# dasblinkenhat-controller-mk-4_2.net
KiCad netlist of a schematic drawn in EAGLE
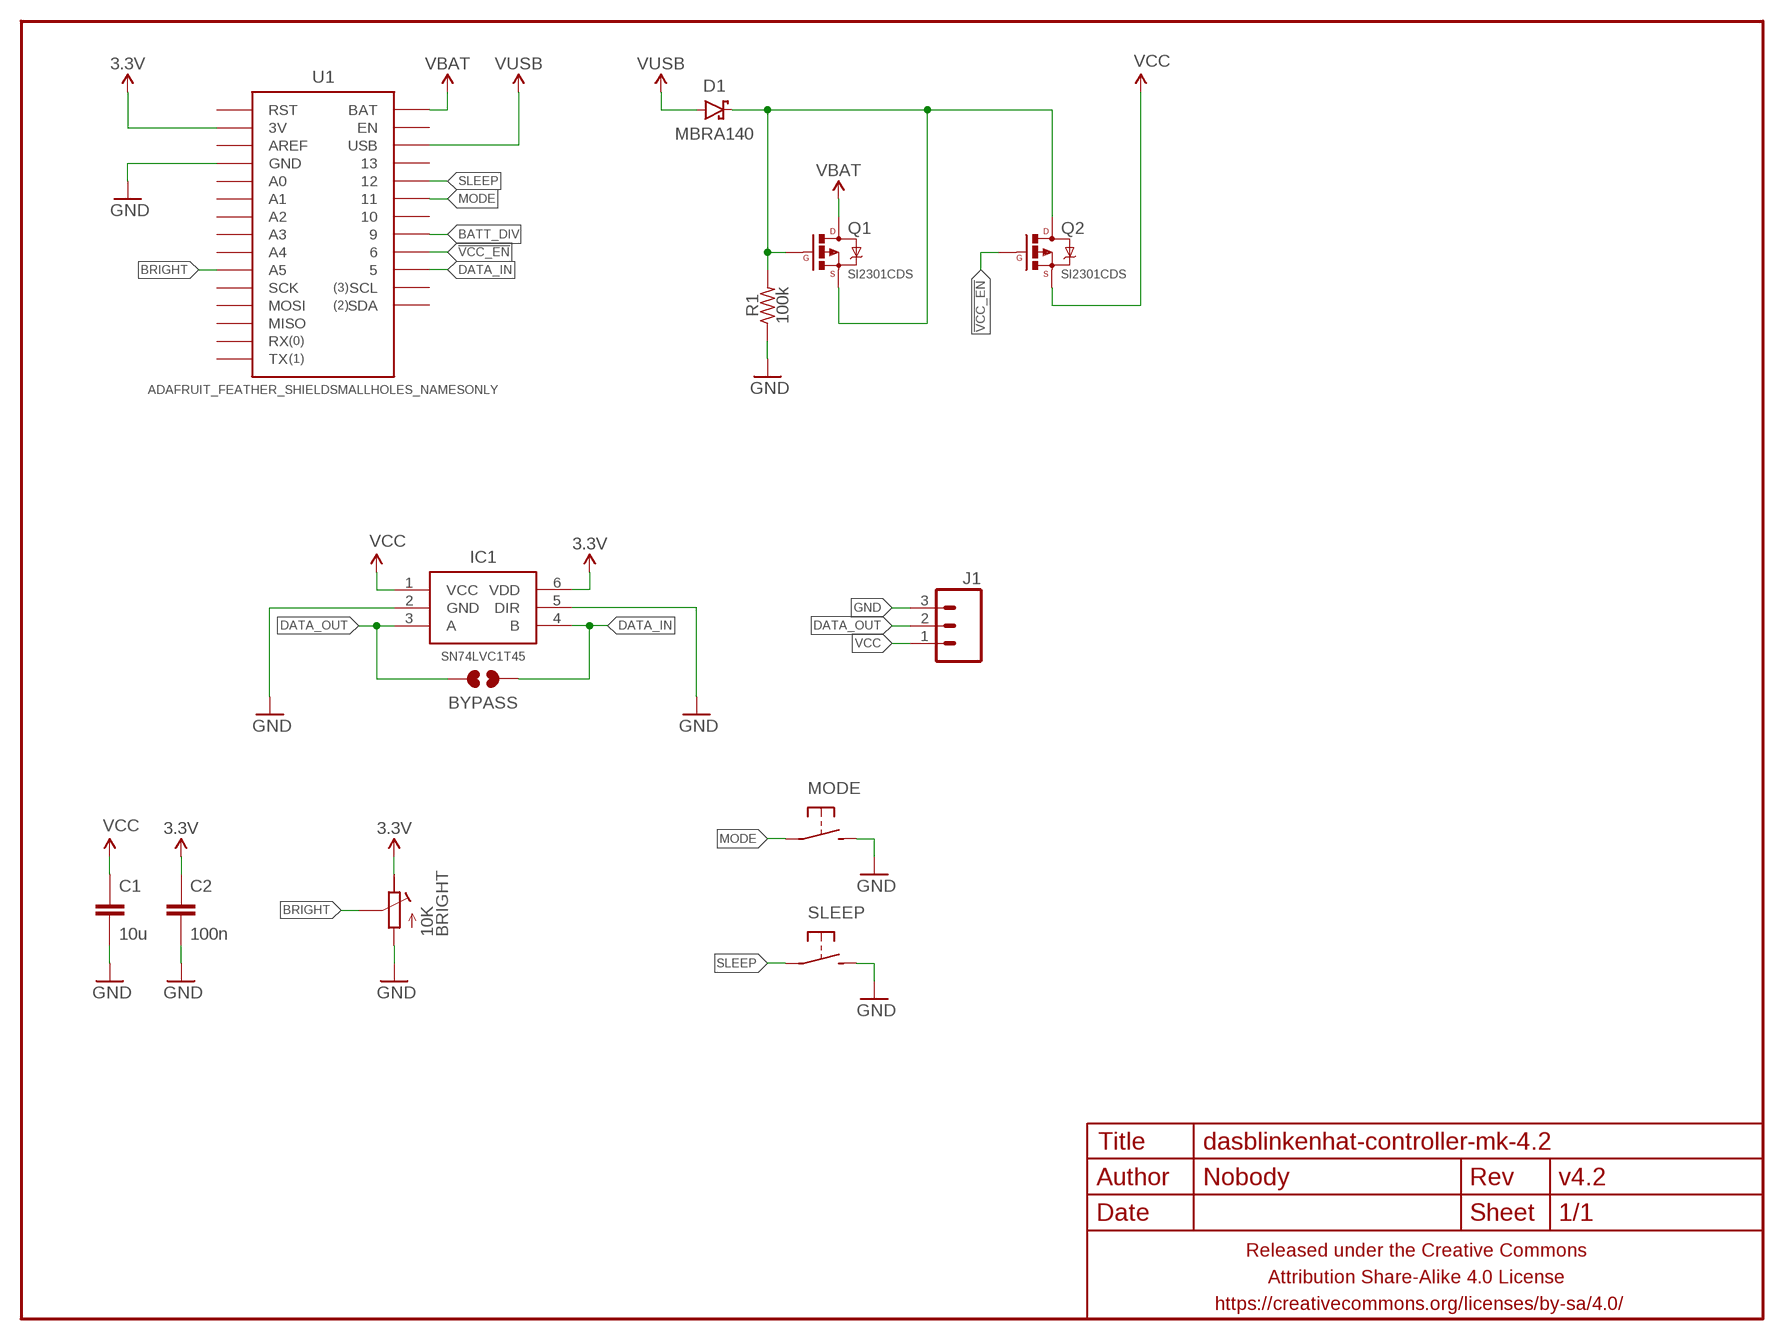
[diagram p0: schematic, sheet 1]

(export (version "E")
  (design (tool "Eeschema 10.0.6"))
  (components
    (comp (ref "BRIGHT")
      (value "10K")
      (footprint "eagle-import:EVM3Y")
      (libsource (lib "eagle-import") (part "POTENTIOMETEREVM3Y"))
    )
    (comp (ref "BYPASS")
      (value "JUMPER-PAD-2-NOYES_SILK")
      (footprint "eagle-import:PAD-JUMPER-2-NO_YES_SILK")
      (libsource (lib "eagle-import") (part "JUMPER-PAD-2-NOYES_SILK"))
    )
    (comp (ref "C1")
      (value "10u")
      (footprint "eagle-import:C0805")
      (libsource (lib "eagle-import") (part "CAPACITOR-CERAMICC0805"))
    )
    (comp (ref "C2")
      (value "100n")
      (footprint "eagle-import:C0603")
      (libsource (lib "eagle-import") (part "CAPACITOR-CERAMICC0603"))
    )
    (comp (ref "D1")
      (value "MBRA140")
      (footprint "eagle-import:SMA-DIODE")
      (libsource (lib "eagle-import") (part "DIODE-SCHOTTKYMBRA140"))
    )
    (comp (ref "FRAME1")
      (value "FRAME-LETTERNO_PACKAGE")
      (footprint "eagle-import:DUMMY")
      (fields (field (name "VERSION") "v4.2") (field (name "DESIGNER") "Nobody"))
      (libsource (lib "eagle-import") (part "FRAME-LETTERNO_PACKAGE"))
    )
    (comp (ref "IC1")
      (value "SN74LVC1T45")
      (footprint "eagle-import:SOT23-6")
      (libsource (lib "eagle-import") (part "SN74LVC1T45SOT23-6"))
    )
    (comp (ref "J1")
      (value "M03JST-XH-RA-PTH")
      (footprint "eagle-import:JST-3-XH-RA-PTH")
      (libsource (lib "eagle-import") (part "M03JST-XH-RA-PTH"))
    )
    (comp (ref "MODE")
      (value "DTS-6MM")
      (footprint "eagle-import:TACTILE-PTH-12MM")
      (libsource (lib "eagle-import") (part "SPST-NO-TACT12MM-PTH"))
    )
    (comp (ref "Q1")
      (value "SI2301CDS")
      (footprint "eagle-import:SOT23")
      (libsource (lib "eagle-import") (part "MOSFET-PCHANNELSOT-23"))
    )
    (comp (ref "Q2")
      (value "SI2301CDS")
      (footprint "eagle-import:SOT23")
      (libsource (lib "eagle-import") (part "MOSFET-PCHANNELSOT-23"))
    )
    (comp (ref "R1")
      (value "100k")
      (footprint "eagle-import:R0603")
      (libsource (lib "eagle-import") (part "RESISTORR0603"))
    )
    (comp (ref "SLEEP")
      (value "DTS-6MM")
      (footprint "eagle-import:TACTILE-PTH-12MM")
      (libsource (lib "eagle-import") (part "SPST-NO-TACT12MM-PTH"))
    )
    (comp (ref "U1")
      (value "ADAFRUIT_FEATHER_SHIELDSMALLHOLES_NAMESONLY")
      (footprint "eagle-import:ADAFRUIT_FEATHER_SMALLHOLES_NAMESONLY")
      (libsource (lib "eagle-import") (part "ADAFRUIT_FEATHER_SHIELDSMALLHOLES_NAMESONLY"))
    )
  )
  (nets
    (net (code "1") (name "/~{VCC_EN}") (class "Default")
      (node (ref "Q2") (pin "1") (pinfunction "G_1") (pintype "passive"))
      (node (ref "U1") (pin "6") (pinfunction "6_6") (pintype "bidirectional"))
    )
    (net (code "2") (name "3.3V") (class "Default")
      (node (ref "BRIGHT") (pin "E") (pinfunction "E_E") (pintype "passive"))
      (node (ref "C2") (pin "1") (pinfunction "1_1") (pintype "passive"))
      (node (ref "IC1") (pin "6") (pinfunction "VDD_6") (pintype "bidirectional"))
      (node (ref "U1") (pin "3V") (pinfunction "3V_3V") (pintype "bidirectional"))
    )
    (net (code "3") (name "BATT_DIV") (class "Default")
      (node (ref "U1") (pin "9") (pinfunction "9_9") (pintype "bidirectional"))
    )
    (net (code "4") (name "BRIGHT") (class "Default")
      (node (ref "BRIGHT") (pin "S") (pinfunction "S_S") (pintype "passive"))
      (node (ref "U1") (pin "A5") (pinfunction "A5_A5") (pintype "bidirectional"))
    )
    (net (code "5") (name "DATA_IN") (class "Default")
      (node (ref "BYPASS") (pin "1") (pinfunction "1_1") (pintype "passive"))
      (node (ref "IC1") (pin "4") (pinfunction "B_4") (pintype "bidirectional"))
      (node (ref "U1") (pin "5") (pinfunction "5_5") (pintype "bidirectional"))
    )
    (net (code "6") (name "DATA_OUT") (class "Default")
      (node (ref "BYPASS") (pin "2") (pinfunction "2_2") (pintype "passive"))
      (node (ref "IC1") (pin "3") (pinfunction "A_3") (pintype "bidirectional"))
      (node (ref "J1") (pin "2") (pinfunction "2_2") (pintype "passive"))
    )
    (net (code "7") (name "GND") (class "Default")
      (node (ref "BRIGHT") (pin "A") (pinfunction "A_A") (pintype "passive"))
      (node (ref "C1") (pin "2") (pinfunction "2_2") (pintype "passive"))
      (node (ref "C2") (pin "2") (pinfunction "2_2") (pintype "passive"))
      (node (ref "IC1") (pin "2") (pinfunction "GND_2") (pintype "bidirectional"))
      (node (ref "IC1") (pin "5") (pinfunction "DIR_5") (pintype "bidirectional"))
      (node (ref "J1") (pin "3") (pinfunction "3_3") (pintype "passive"))
      (node (ref "MODE") (pin "3") (pinfunction "2_3") (pintype "passive"))
      (node (ref "MODE") (pin "4") (pinfunction "2_4") (pintype "passive"))
      (node (ref "R1") (pin "1") (pinfunction "1_1") (pintype "passive"))
      (node (ref "SLEEP") (pin "3") (pinfunction "2_3") (pintype "passive"))
      (node (ref "SLEEP") (pin "4") (pinfunction "2_4") (pintype "passive"))
      (node (ref "U1") (pin "GND@0") (pinfunction "GND_GND@0") (pintype "bidirectional"))
      (node (ref "U1") (pin "GND@1") (pinfunction "GND_GND@1") (pintype "bidirectional"))
    )
    (net (code "8") (name "MODE") (class "Default")
      (node (ref "MODE") (pin "1") (pinfunction "1_1") (pintype "passive"))
      (node (ref "MODE") (pin "2") (pinfunction "1_2") (pintype "passive"))
      (node (ref "U1") (pin "11") (pinfunction "11_11") (pintype "bidirectional"))
    )
    (net (code "9") (name "Net-(Q1-G)") (class "Default")
      (node (ref "D1") (pin "C") (pinfunction "C_C") (pintype "passive"))
      (node (ref "Q1") (pin "1") (pinfunction "G_1") (pintype "passive"))
      (node (ref "Q1") (pin "2") (pinfunction "S_2") (pintype "passive"))
      (node (ref "Q2") (pin "3") (pinfunction "D_3") (pintype "passive"))
      (node (ref "R1") (pin "2") (pinfunction "2_2") (pintype "passive"))
    )
    (net (code "10") (name "SLEEP") (class "Default")
      (node (ref "SLEEP") (pin "1") (pinfunction "1_1") (pintype "passive"))
      (node (ref "SLEEP") (pin "2") (pinfunction "1_2") (pintype "passive"))
      (node (ref "U1") (pin "12") (pinfunction "12_12") (pintype "bidirectional"))
    )
    (net (code "11") (name "VBAT") (class "Default")
      (node (ref "Q1") (pin "3") (pinfunction "D_3") (pintype "passive"))
      (node (ref "U1") (pin "BAT") (pinfunction "BAT_BAT") (pintype "bidirectional"))
    )
    (net (code "12") (name "VCC") (class "Default")
      (node (ref "C1") (pin "1") (pinfunction "1_1") (pintype "passive"))
      (node (ref "IC1") (pin "1") (pinfunction "VCC_1") (pintype "bidirectional"))
      (node (ref "J1") (pin "1") (pinfunction "1_1") (pintype "passive"))
      (node (ref "Q2") (pin "2") (pinfunction "S_2") (pintype "passive"))
    )
    (net (code "13") (name "VUSB") (class "Default")
      (node (ref "D1") (pin "A") (pinfunction "A_A") (pintype "passive"))
      (node (ref "U1") (pin "USB") (pinfunction "USB_USB") (pintype "bidirectional"))
    )
    (net (code "14") (name "unconnected-(U1-Pad10)") (class "Default")
      (node (ref "U1") (pin "10") (pinfunction "10_10") (pintype "bidirectional"))
    )
    (net (code "15") (name "unconnected-(U1-Pad13)") (class "Default")
      (node (ref "U1") (pin "13") (pinfunction "13_13") (pintype "bidirectional"))
    )
    (net (code "16") (name "unconnected-(U1-PadA0)") (class "Default")
      (node (ref "U1") (pin "A0") (pinfunction "A0_A0") (pintype "bidirectional"))
    )
    (net (code "17") (name "unconnected-(U1-PadA1)") (class "Default")
      (node (ref "U1") (pin "A1") (pinfunction "A1_A1") (pintype "bidirectional"))
    )
    (net (code "18") (name "unconnected-(U1-PadA2)") (class "Default")
      (node (ref "U1") (pin "A2") (pinfunction "A2_A2") (pintype "bidirectional"))
    )
    (net (code "19") (name "unconnected-(U1-PadA3)") (class "Default")
      (node (ref "U1") (pin "A3") (pinfunction "A3_A3") (pintype "bidirectional"))
    )
    (net (code "20") (name "unconnected-(U1-PadA4)") (class "Default")
      (node (ref "U1") (pin "A4") (pinfunction "A4_A4") (pintype "bidirectional"))
    )
    (net (code "21") (name "unconnected-(U1-PadAREF)") (class "Default")
      (node (ref "U1") (pin "AREF") (pinfunction "AREF_AREF") (pintype "bidirectional"))
    )
    (net (code "22") (name "unconnected-(U1-PadEN)") (class "Default")
      (node (ref "U1") (pin "EN") (pinfunction "EN_EN") (pintype "bidirectional"))
    )
    (net (code "23") (name "unconnected-(U1-PadMISO)") (class "Default")
      (node (ref "U1") (pin "MISO") (pinfunction "MISO_MISO") (pintype "bidirectional"))
    )
    (net (code "24") (name "unconnected-(U1-PadMOSI)") (class "Default")
      (node (ref "U1") (pin "MOSI") (pinfunction "MOSI_MOSI") (pintype "bidirectional"))
    )
    (net (code "25") (name "unconnected-(U1-PadRST)") (class "Default")
      (node (ref "U1") (pin "RST") (pinfunction "RST_RST") (pintype "bidirectional"))
    )
    (net (code "26") (name "unconnected-(U1-PadRX)") (class "Default")
      (node (ref "U1") (pin "RX") (pinfunction "RX_RX") (pintype "bidirectional"))
    )
    (net (code "27") (name "unconnected-(U1-PadSCK)") (class "Default")
      (node (ref "U1") (pin "SCK") (pinfunction "SCK_SCK") (pintype "bidirectional"))
    )
    (net (code "28") (name "unconnected-(U1-PadSCL)") (class "Default")
      (node (ref "U1") (pin "SCL") (pinfunction "SCL_SCL") (pintype "bidirectional"))
    )
    (net (code "29") (name "unconnected-(U1-PadSDA)") (class "Default")
      (node (ref "U1") (pin "SDA") (pinfunction "SDA_SDA") (pintype "bidirectional"))
    )
    (net (code "30") (name "unconnected-(U1-PadTX)") (class "Default")
      (node (ref "U1") (pin "TX") (pinfunction "TX_TX") (pintype "bidirectional"))
    )
  )
)
